# arduino_micro_based.net
KiCad netlist of a schematic drawn in EAGLE
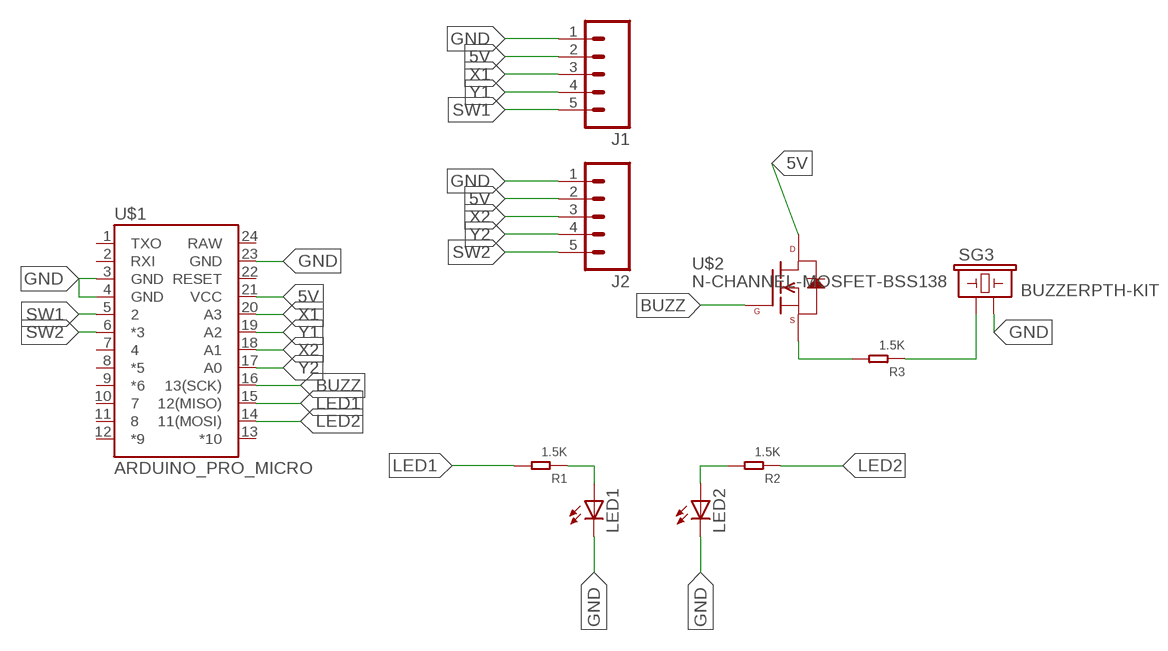
[diagram p0: schematic, sheet 1]

(export (version "E")
  (design (tool "Eeschema 10.0.6"))
  (components
    (comp (ref "J1")
      (value "M05JST-VERT")
      (footprint "eagle-import:JST-5-PTH-VERT")
      (libsource (lib "eagle-import") (part "M05JST-VERT"))
    )
    (comp (ref "J2")
      (value "M05JST-VERT")
      (footprint "eagle-import:JST-5-PTH-VERT")
      (libsource (lib "eagle-import") (part "M05JST-VERT"))
    )
    (comp (ref "LED1")
      (value "LED5MM")
      (footprint "eagle-import:LED5MM")
      (libsource (lib "eagle-import") (part "LED5MM"))
    )
    (comp (ref "LED2")
      (value "LED5MM")
      (footprint "eagle-import:LED5MM")
      (libsource (lib "eagle-import") (part "LED5MM"))
    )
    (comp (ref "R1")
      (value "1.5K")
      (footprint "eagle-import:R0603")
      (fields (field (name "MPN") "RC0603FR-071K5L"))
      (libsource (lib "eagle-import") (part "SMD-RES-1.5K-1%-1/10W(0603)"))
    )
    (comp (ref "R2")
      (value "1.5K")
      (footprint "eagle-import:R0603")
      (fields (field (name "MPN") "RC0603FR-071K5L"))
      (libsource (lib "eagle-import") (part "SMD-RES-1.5K-1%-1/10W(0603)"))
    )
    (comp (ref "R3")
      (value "1.5K")
      (footprint "eagle-import:R0603")
      (fields (field (name "MPN") "RC0603FR-071K5L"))
      (libsource (lib "eagle-import") (part "SMD-RES-1.5K-1%-1/10W(0603)"))
    )
    (comp (ref "SG3")
      (value "BUZZERPTH-KIT")
      (footprint "eagle-import:BUZZER-12MM-KIT")
      (libsource (lib "eagle-import") (part "BUZZERPTH-KIT"))
    )
    (comp (ref "U$1")
      (value "ARDUINO_PRO_MICRO")
      (footprint "eagle-import:ARDUINO_PRO_MICRO")
      (libsource (lib "eagle-import") (part "ARDUINO_PRO_MICRO"))
    )
    (comp (ref "U$2")
      (value "N-CHANNEL-MOSFET-BSS138")
      (footprint "eagle-import:SOT23-3")
      (libsource (lib "eagle-import") (part "N-CHANNEL-MOSFET-BSS138"))
    )
  )
  (nets
    (net (code "1") (name "5V") (class "Default")
      (node (ref "J1") (pin "2") (pinfunction "2_2") (pintype "passive"))
      (node (ref "J2") (pin "2") (pinfunction "2_2") (pintype "passive"))
      (node (ref "U$1") (pin "21") (pinfunction "VCC_21") (pintype "bidirectional"))
      (node (ref "U$2") (pin "3") (pinfunction "D_3") (pintype "passive"))
    )
    (net (code "2") (name "BUZZ") (class "Default")
      (node (ref "U$1") (pin "16") (pinfunction "13(SCK)_16") (pintype "bidirectional"))
      (node (ref "U$2") (pin "1") (pinfunction "G_1") (pintype "passive"))
    )
    (net (code "3") (name "GND") (class "Default")
      (node (ref "J1") (pin "1") (pinfunction "1_1") (pintype "passive"))
      (node (ref "J2") (pin "1") (pinfunction "1_1") (pintype "passive"))
      (node (ref "LED1") (pin "K") (pinfunction "C_K") (pintype "passive"))
      (node (ref "LED2") (pin "K") (pinfunction "C_K") (pintype "passive"))
      (node (ref "SG3") (pin "-") (pinfunction "2_-") (pintype "passive"))
      (node (ref "U$1") (pin "23") (pinfunction "GND_23") (pintype "bidirectional"))
      (node (ref "U$1") (pin "3") (pinfunction "GND_3") (pintype "bidirectional"))
      (node (ref "U$1") (pin "4") (pinfunction "GND_4") (pintype "bidirectional"))
    )
    (net (code "4") (name "LED1") (class "Default")
      (node (ref "R1") (pin "2") (pinfunction "2_2") (pintype "passive"))
      (node (ref "U$1") (pin "15") (pinfunction "12(MISO)_15") (pintype "bidirectional"))
    )
    (net (code "5") (name "LED2") (class "Default")
      (node (ref "R2") (pin "1") (pinfunction "1_1") (pintype "passive"))
      (node (ref "U$1") (pin "14") (pinfunction "11(MOSI)_14") (pintype "bidirectional"))
    )
    (net (code "6") (name "Net-(LED1-PadA)") (class "Default")
      (node (ref "LED1") (pin "A") (pinfunction "A_A") (pintype "passive"))
      (node (ref "R1") (pin "1") (pinfunction "1_1") (pintype "passive"))
    )
    (net (code "7") (name "Net-(LED2-PadA)") (class "Default")
      (node (ref "LED2") (pin "A") (pinfunction "A_A") (pintype "passive"))
      (node (ref "R2") (pin "2") (pinfunction "2_2") (pintype "passive"))
    )
    (net (code "8") (name "Net-(SG3-1)") (class "Default")
      (node (ref "R3") (pin "1") (pinfunction "1_1") (pintype "passive"))
      (node (ref "SG3") (pin "+") (pinfunction "1_+") (pintype "passive"))
    )
    (net (code "9") (name "Net-(U$2-S)") (class "Default")
      (node (ref "R3") (pin "2") (pinfunction "2_2") (pintype "passive"))
      (node (ref "U$2") (pin "2") (pinfunction "S_2") (pintype "passive"))
    )
    (net (code "10") (name "SW1") (class "Default")
      (node (ref "J1") (pin "5") (pinfunction "5_5") (pintype "passive"))
      (node (ref "U$1") (pin "5") (pinfunction "2_5") (pintype "bidirectional"))
    )
    (net (code "11") (name "SW2") (class "Default")
      (node (ref "J2") (pin "5") (pinfunction "5_5") (pintype "passive"))
      (node (ref "U$1") (pin "6") (pinfunction "*3_6") (pintype "bidirectional"))
    )
    (net (code "12") (name "X1") (class "Default")
      (node (ref "J1") (pin "3") (pinfunction "3_3") (pintype "passive"))
      (node (ref "U$1") (pin "20") (pinfunction "A3_20") (pintype "bidirectional"))
    )
    (net (code "13") (name "X2") (class "Default")
      (node (ref "J2") (pin "3") (pinfunction "3_3") (pintype "passive"))
      (node (ref "U$1") (pin "18") (pinfunction "A1_18") (pintype "bidirectional"))
    )
    (net (code "14") (name "Y1") (class "Default")
      (node (ref "J1") (pin "4") (pinfunction "4_4") (pintype "passive"))
      (node (ref "U$1") (pin "19") (pinfunction "A2_19") (pintype "bidirectional"))
    )
    (net (code "15") (name "Y2") (class "Default")
      (node (ref "J2") (pin "4") (pinfunction "4_4") (pintype "passive"))
      (node (ref "U$1") (pin "17") (pinfunction "A0_17") (pintype "bidirectional"))
    )
    (net (code "16") (name "unconnected-(U$1-*5-Pad8)") (class "Default")
      (node (ref "U$1") (pin "8") (pinfunction "*5_8") (pintype "bidirectional"))
    )
    (net (code "17") (name "unconnected-(U$1-*6-Pad9)") (class "Default")
      (node (ref "U$1") (pin "9") (pinfunction "*6_9") (pintype "bidirectional"))
    )
    (net (code "18") (name "unconnected-(U$1-*9-Pad12)") (class "Default")
      (node (ref "U$1") (pin "12") (pinfunction "*9_12") (pintype "bidirectional"))
    )
    (net (code "19") (name "unconnected-(U$1-*10-Pad13)") (class "Default")
      (node (ref "U$1") (pin "13") (pinfunction "*10_13") (pintype "bidirectional"))
    )
    (net (code "20") (name "unconnected-(U$1-4-Pad7)") (class "Default")
      (node (ref "U$1") (pin "7") (pinfunction "4_7") (pintype "bidirectional"))
    )
    (net (code "21") (name "unconnected-(U$1-7-Pad10)") (class "Default")
      (node (ref "U$1") (pin "10") (pinfunction "7_10") (pintype "bidirectional"))
    )
    (net (code "22") (name "unconnected-(U$1-8-Pad11)") (class "Default")
      (node (ref "U$1") (pin "11") (pinfunction "8_11") (pintype "bidirectional"))
    )
    (net (code "23") (name "unconnected-(U$1-RAW-Pad24)") (class "Default")
      (node (ref "U$1") (pin "24") (pinfunction "RAW_24") (pintype "bidirectional"))
    )
    (net (code "24") (name "unconnected-(U$1-RESET-Pad22)") (class "Default")
      (node (ref "U$1") (pin "22") (pinfunction "RESET_22") (pintype "bidirectional"))
    )
    (net (code "25") (name "unconnected-(U$1-RXI-Pad2)") (class "Default")
      (node (ref "U$1") (pin "2") (pinfunction "RXI_2") (pintype "bidirectional"))
    )
    (net (code "26") (name "unconnected-(U$1-TXO-Pad1)") (class "Default")
      (node (ref "U$1") (pin "1") (pinfunction "TXO_1") (pintype "bidirectional"))
    )
  )
)
